# PMTControl.net
KiCad netlist of a schematic drawn in Altium Designer
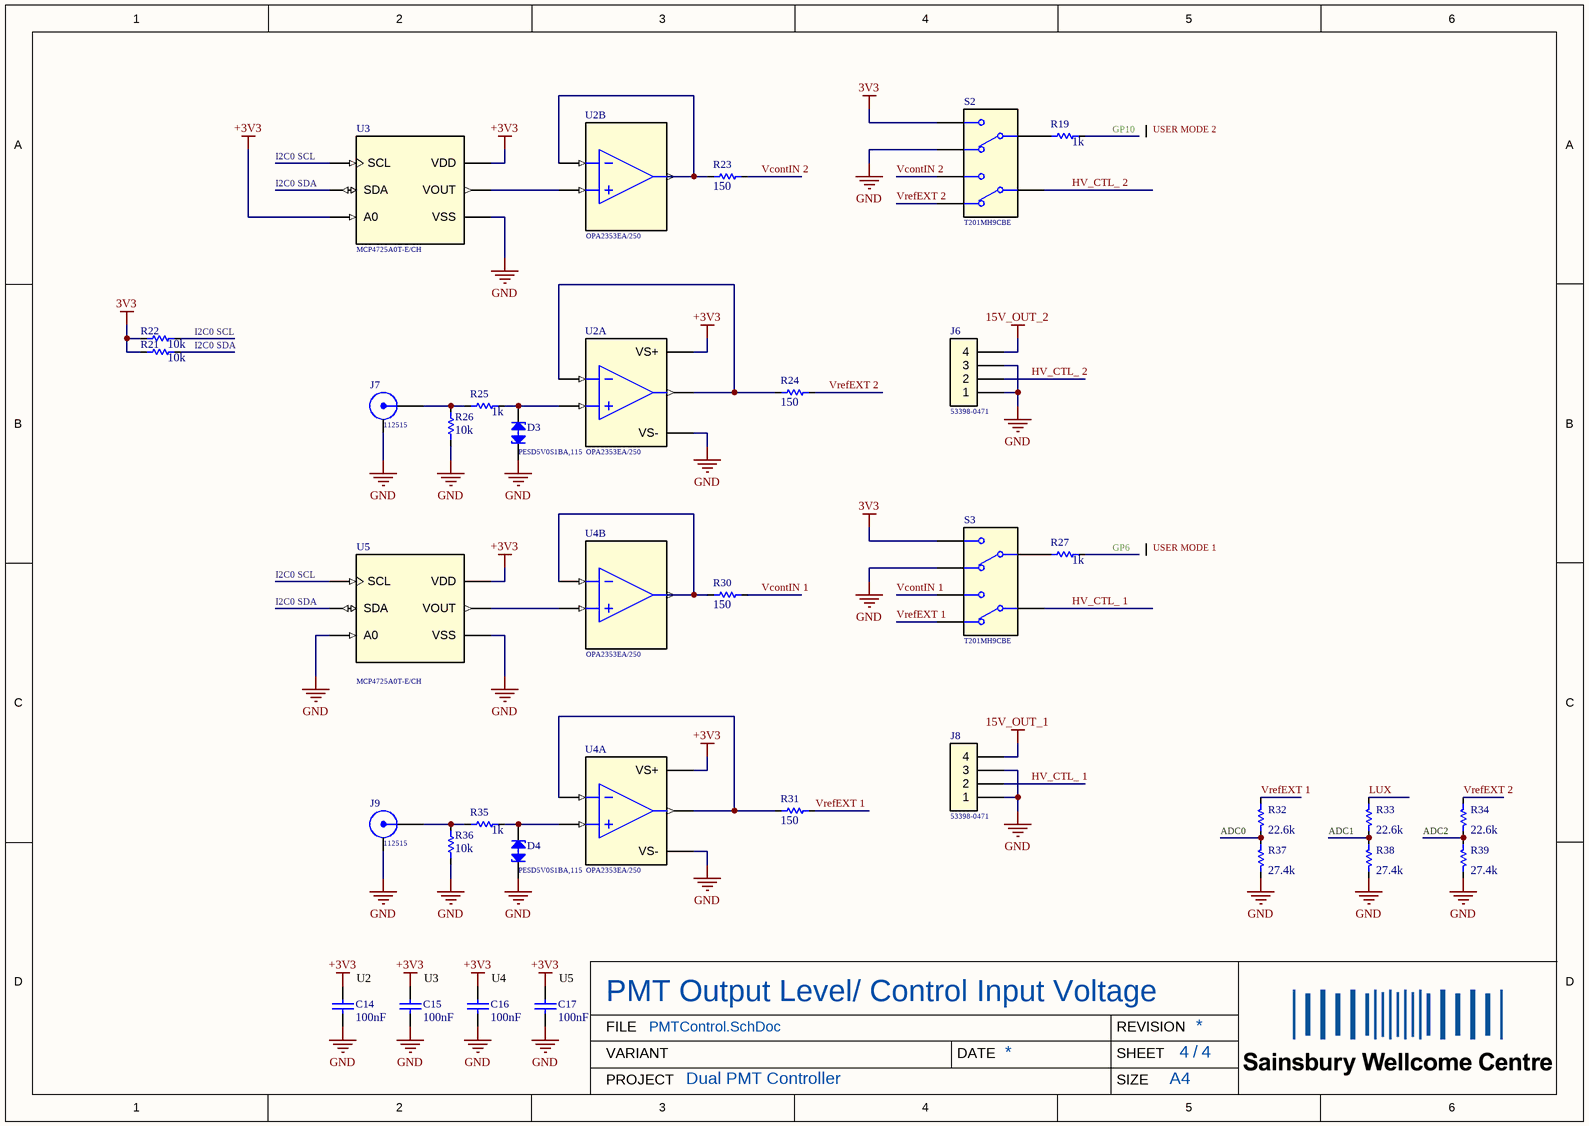
[diagram p0: PMTControl.SchDoc]

(export (version "E")
  (design (tool "Eeschema 10.0.6"))
  (components
    (comp (ref "C14")
      (value "100nF")
      (footprint "FP-GRM188-0_1-e0_2_0_5-IPC_B")
      (description "0.1µF ±10% 100V Ceramic Capacitor X7R 0603 (1608 Metric)")
      (fields (field (name "TOLERANCE") "10%") (field (name "VOLTAGE") "100V"))
      (libsource (lib "Sainsbury Wellcome Centre") (part "Cap"))
    )
    (comp (ref "C15")
      (value "100nF")
      (footprint "FP-GRM188-0_1-e0_2_0_5-IPC_B")
      (description "0.1µF ±10% 100V Ceramic Capacitor X7R 0603 (1608 Metric)")
      (fields (field (name "TOLERANCE") "10%") (field (name "VOLTAGE") "100V"))
      (libsource (lib "Sainsbury Wellcome Centre") (part "Cap"))
    )
    (comp (ref "C16")
      (value "100nF")
      (footprint "FP-GRM188-0_1-e0_2_0_5-IPC_B")
      (description "0.1µF ±10% 100V Ceramic Capacitor X7R 0603 (1608 Metric)")
      (fields (field (name "TOLERANCE") "10%") (field (name "VOLTAGE") "100V"))
      (libsource (lib "Sainsbury Wellcome Centre") (part "Cap"))
    )
    (comp (ref "C17")
      (value "100nF")
      (footprint "FP-GRM188-0_1-e0_2_0_5-IPC_B")
      (description "0.1µF ±10% 100V Ceramic Capacitor X7R 0603 (1608 Metric)")
      (fields (field (name "TOLERANCE") "10%") (field (name "VOLTAGE") "100V"))
      (libsource (lib "Sainsbury Wellcome Centre") (part "Cap"))
    )
    (comp (ref "D3")
      (value "PESD5V0S1BA,115")
      (footprint "FP-SOD323-CA-IPC_B")
      (description "Trans Voltage Suppressor Diode, 130W, 5V V(RWM), Bidirectional, 1 Element, Silicon")
      (libsource (lib "Sainsbury Wellcome Centre") (part "BI-ESD"))
    )
    (comp (ref "D4")
      (value "PESD5V0S1BA,115")
      (footprint "FP-SOD323-CA-IPC_B")
      (description "Trans Voltage Suppressor Diode, 130W, 5V V(RWM), Bidirectional, 1 Element, Silicon")
      (libsource (lib "Sainsbury Wellcome Centre") (part "BI-ESD"))
    )
    (comp (ref "J6")
      (value "53398-0471")
      (footprint "FP-533980471-MFG")
      (libsource (lib "Sainsbury Wellcome Centre") (part "Jack 4x1"))
    )
    (comp (ref "J7")
      (value "112515")
      (footprint "AMP_112515")
      (description "RF BNC Connector, Female, Board Mount, Solder Terminal, Jack")
      (libsource (lib "Sainsbury Wellcome Centre") (part "RF-Jack-V2"))
    )
    (comp (ref "J8")
      (value "53398-0471")
      (footprint "FP-533980471-MFG")
      (libsource (lib "Sainsbury Wellcome Centre") (part "Jack 4x1"))
    )
    (comp (ref "J9")
      (value "112515")
      (footprint "AMP_112515")
      (description "RF BNC Connector, Female, Board Mount, Solder Terminal, Jack")
      (libsource (lib "Sainsbury Wellcome Centre") (part "RF-Jack-V2"))
    )
    (comp (ref "R19")
      (value "1k")
      (footprint "FP-CPF0603-IPC_B")
      (description "Surface Mount Resistor 1k Ohm 1/16 W 0.1% 0603 (1608 Metric)")
      (fields (field (name "TOLERANCE") "0.1%") (field (name "Comment") "R0603-1k-1/16W-0.1%"))
      (libsource (lib "Sainsbury Wellcome Centre") (part "Res"))
    )
    (comp (ref "R21")
      (value "10k")
      (footprint "FP-CPF0603-IPC_B")
      (description "Surface Mount Resistor 10k Ohm 1/16 W 0.1% 0603 (1608 Metric)")
      (fields (field (name "TOLERANCE") "0.1%") (field (name "Comment") "R0603-10k-1/16W-0.1%"))
      (libsource (lib "Sainsbury Wellcome Centre") (part "Res"))
    )
    (comp (ref "R22")
      (value "10k")
      (footprint "FP-CPF0603-IPC_B")
      (description "Surface Mount Resistor 10k Ohm 1/16 W 0.1% 0603 (1608 Metric)")
      (fields (field (name "TOLERANCE") "0.1%") (field (name "Comment") "R0603-10k-1/16W-0.1%"))
      (libsource (lib "Sainsbury Wellcome Centre") (part "Res"))
    )
    (comp (ref "R23")
      (value "150")
      (footprint "FP-CPF0603-IPC_B")
      (description "Surface Mount Resistor 150 Ohm 1/16 W 0.1% 0603 (1608 Metric)")
      (fields (field (name "TOLERANCE") "0.1%") (field (name "Comment") "R0603-150R-1/16W-0.1%"))
      (libsource (lib "Sainsbury Wellcome Centre") (part "Res"))
    )
    (comp (ref "R24")
      (value "150")
      (footprint "FP-CPF0603-IPC_B")
      (description "Surface Mount Resistor 150 Ohm 1/16 W 0.1% 0603 (1608 Metric)")
      (fields (field (name "TOLERANCE") "0.1%") (field (name "Comment") "R0603-150R-1/16W-0.1%"))
      (libsource (lib "Sainsbury Wellcome Centre") (part "Res"))
    )
    (comp (ref "R25")
      (value "1k")
      (footprint "FP-CPF0603-IPC_B")
      (description "Surface Mount Resistor 1k Ohm 1/16 W 0.1% 0603 (1608 Metric)")
      (fields (field (name "TOLERANCE") "0.1%") (field (name "Comment") "R0603-1k-1/16W-0.1%"))
      (libsource (lib "Sainsbury Wellcome Centre") (part "Res"))
    )
    (comp (ref "R26")
      (value "10k")
      (footprint "FP-CPF0603-IPC_B")
      (description "Surface Mount Resistor 10k Ohm 1/16 W 0.1% 0603 (1608 Metric)")
      (fields (field (name "TOLERANCE") "0.1%") (field (name "Comment") "R0603-10k-1/16W-0.1%"))
      (libsource (lib "Sainsbury Wellcome Centre") (part "Res"))
    )
    (comp (ref "R27")
      (value "1k")
      (footprint "FP-CPF0603-IPC_B")
      (description "Surface Mount Resistor 1k Ohm 1/16 W 0.1% 0603 (1608 Metric)")
      (fields (field (name "TOLERANCE") "0.1%") (field (name "Comment") "R0603-1k-1/16W-0.1%"))
      (libsource (lib "Sainsbury Wellcome Centre") (part "Res"))
    )
    (comp (ref "R30")
      (value "150")
      (footprint "FP-CPF0603-IPC_B")
      (description "Surface Mount Resistor 150 Ohm 1/16 W 0.1% 0603 (1608 Metric)")
      (fields (field (name "TOLERANCE") "0.1%") (field (name "Comment") "R0603-150R-1/16W-0.1%"))
      (libsource (lib "Sainsbury Wellcome Centre") (part "Res"))
    )
    (comp (ref "R31")
      (value "150")
      (footprint "FP-CPF0603-IPC_B")
      (description "Surface Mount Resistor 150 Ohm 1/16 W 0.1% 0603 (1608 Metric)")
      (fields (field (name "TOLERANCE") "0.1%") (field (name "Comment") "R0603-150R-1/16W-0.1%"))
      (libsource (lib "Sainsbury Wellcome Centre") (part "Res"))
    )
    (comp (ref "R32")
      (value "22.6k")
      (footprint "FP-CPF0603-IPC_B")
      (description "Surface Mount Resistor 22.6k Ohm 1/16 W 0.1% 0603 (1608 Metric)")
      (fields (field (name "TOLERANCE") "0.1%") (field (name "Comment") "R0603-22k6-1/16W-0.1%"))
      (libsource (lib "Sainsbury Wellcome Centre") (part "Res"))
    )
    (comp (ref "R33")
      (value "22.6k")
      (footprint "FP-CPF0603-IPC_B")
      (description "Surface Mount Resistor 22.6k Ohm 1/16 W 0.1% 0603 (1608 Metric)")
      (fields (field (name "TOLERANCE") "0.1%") (field (name "Comment") "R0603-22k6-1/16W-0.1%"))
      (libsource (lib "Sainsbury Wellcome Centre") (part "Res"))
    )
    (comp (ref "R34")
      (value "22.6k")
      (footprint "FP-CPF0603-IPC_B")
      (description "Surface Mount Resistor 22.6k Ohm 1/16 W 0.1% 0603 (1608 Metric)")
      (fields (field (name "TOLERANCE") "0.1%") (field (name "Comment") "R0603-22k6-1/16W-0.1%"))
      (libsource (lib "Sainsbury Wellcome Centre") (part "Res"))
    )
    (comp (ref "R35")
      (value "1k")
      (footprint "FP-CPF0603-IPC_B")
      (description "Surface Mount Resistor 1k Ohm 1/16 W 0.1% 0603 (1608 Metric)")
      (fields (field (name "TOLERANCE") "0.1%") (field (name "Comment") "R0603-1k-1/16W-0.1%"))
      (libsource (lib "Sainsbury Wellcome Centre") (part "Res"))
    )
    (comp (ref "R36")
      (value "10k")
      (footprint "FP-CPF0603-IPC_B")
      (description "Surface Mount Resistor 10k Ohm 1/16 W 0.1% 0603 (1608 Metric)")
      (fields (field (name "TOLERANCE") "0.1%") (field (name "Comment") "R0603-10k-1/16W-0.1%"))
      (libsource (lib "Sainsbury Wellcome Centre") (part "Res"))
    )
    (comp (ref "R37")
      (value "27.4k")
      (footprint "FP-CPF0603-IPC_B")
      (description "Surface Mount Resistor 27.4k Ohm 1/16 W 0.1% 0603 (1608 Metric)")
      (fields (field (name "TOLERANCE") "0.1%") (field (name "Comment") "R0603-27k4-1/16W-0.1%"))
      (libsource (lib "Sainsbury Wellcome Centre") (part "Res"))
    )
    (comp (ref "R38")
      (value "27.4k")
      (footprint "FP-CPF0603-IPC_B")
      (description "Surface Mount Resistor 27.4k Ohm 1/16 W 0.1% 0603 (1608 Metric)")
      (fields (field (name "TOLERANCE") "0.1%") (field (name "Comment") "R0603-27k4-1/16W-0.1%"))
      (libsource (lib "Sainsbury Wellcome Centre") (part "Res"))
    )
    (comp (ref "R39")
      (value "27.4k")
      (footprint "FP-CPF0603-IPC_B")
      (description "Surface Mount Resistor 27.4k Ohm 1/16 W 0.1% 0603 (1608 Metric)")
      (fields (field (name "TOLERANCE") "0.1%") (field (name "Comment") "R0603-27k4-1/16W-0.1%"))
      (libsource (lib "Sainsbury Wellcome Centre") (part "Res"))
    )
    (comp (ref "S2")
      (value "T201MH9CBE")
      (footprint "SWITCH_T201MH9CBE")
      (libsource (lib "Sainsbury Wellcome Centre") (part "T201MH9CBE"))
    )
    (comp (ref "S3")
      (value "T201MH9CBE")
      (footprint "SWITCH_T201MH9CBE")
      (libsource (lib "Sainsbury Wellcome Centre") (part "T201MH9CBE"))
    )
    (comp (ref "U2")
      (value "OPA2353EA/250")
      (footprint "DGK0008A_N")
      (description "Operational Amplifier, 2 Func, 8000uV Offset-Max, CMOS, PDSO8")
      (libsource (lib "Sainsbury Wellcome Centre") (part "TI-OPA-8_2"))
    )
    (comp (ref "U3")
      (value "MCP4725A0T-E/CH")
      (footprint "FP-C04-028-CHY-MFG")
      (description "DAC 1-CH Resistor-String 12-bit 6-Pin SOT-23A T/R")
      (libsource (lib "Sainsbury Wellcome Centre") (part "13d1b9b03173b6bd00baa384b893ce8"))
    )
    (comp (ref "U4")
      (value "OPA2353EA/250")
      (footprint "DGK0008A_N")
      (description "Operational Amplifier, 2 Func, 8000uV Offset-Max, CMOS, PDSO8")
      (libsource (lib "Sainsbury Wellcome Centre") (part "TI-OPA-8_2"))
    )
    (comp (ref "U5")
      (value "MCP4725A0T-E/CH")
      (footprint "FP-C04-028-CHY-MFG")
      (description "DAC 1-CH Resistor-String 12-bit 6-Pin SOT-23A T/R")
      (libsource (lib "Sainsbury Wellcome Centre") (part "13d1b9b03173b6bd00baa384b893ce8"))
    )
  )
  (nets
    (net (code "1") (name "+3V3") (class "Default")
      (node (ref "C14") (pin "2") (pinfunction "2_2") (pintype "passive"))
      (node (ref "C15") (pin "2") (pinfunction "2_2") (pintype "passive"))
      (node (ref "C16") (pin "2") (pinfunction "2_2") (pintype "passive"))
      (node (ref "C17") (pin "2") (pinfunction "2_2") (pintype "passive"))
      (node (ref "U2") (pin "8") (pinfunction "VS+_8") (pintype "power_in"))
      (node (ref "U3") (pin "3") (pinfunction "VDD_3") (pintype "power_in"))
      (node (ref "U3") (pin "6") (pinfunction "A0_6") (pintype "input"))
      (node (ref "U4") (pin "8") (pinfunction "VS+_8") (pintype "power_in"))
      (node (ref "U5") (pin "3") (pinfunction "VDD_3") (pintype "power_in"))
    )
    (net (code "2") (name "/ADC0") (class "Default")
      (node (ref "R32") (pin "1") (pinfunction "1_1") (pintype "passive"))
      (node (ref "R37") (pin "2") (pinfunction "2_2") (pintype "passive"))
    )
    (net (code "3") (name "/ADC1") (class "Default")
      (node (ref "R33") (pin "1") (pinfunction "1_1") (pintype "passive"))
      (node (ref "R38") (pin "2") (pinfunction "2_2") (pintype "passive"))
    )
    (net (code "4") (name "/ADC2") (class "Default")
      (node (ref "R34") (pin "1") (pinfunction "1_1") (pintype "passive"))
      (node (ref "R39") (pin "2") (pinfunction "2_2") (pintype "passive"))
    )
    (net (code "5") (name "/GP6") (class "Default")
      (node (ref "R27") (pin "2") (pinfunction "2_2") (pintype "passive"))
    )
    (net (code "6") (name "/GP10") (class "Default")
      (node (ref "R19") (pin "2") (pinfunction "2_2") (pintype "passive"))
    )
    (net (code "7") (name "/HV_CTL_ 1") (class "Default")
      (node (ref "J8") (pin "2") (pinfunction "2_2") (pintype "passive"))
      (node (ref "S3") (pin "5") (pinfunction "COMMON_5") (pintype "passive"))
    )
    (net (code "8") (name "/HV_CTL_ 2") (class "Default")
      (node (ref "J6") (pin "2") (pinfunction "2_2") (pintype "passive"))
      (node (ref "S2") (pin "5") (pinfunction "COMMON_5") (pintype "passive"))
    )
    (net (code "9") (name "/I2C0 SCL") (class "Default")
      (node (ref "R22") (pin "1") (pinfunction "1_1") (pintype "passive"))
      (node (ref "U3") (pin "5") (pinfunction "SCL_5") (pintype "input"))
      (node (ref "U5") (pin "5") (pinfunction "SCL_5") (pintype "input"))
    )
    (net (code "10") (name "/I2C0 SDA") (class "Default")
      (node (ref "R21") (pin "1") (pinfunction "1_1") (pintype "passive"))
      (node (ref "U3") (pin "4") (pinfunction "SDA_4") (pintype "bidirectional"))
      (node (ref "U5") (pin "4") (pinfunction "SDA_4") (pintype "bidirectional"))
    )
    (net (code "11") (name "/LUX") (class "Default")
      (node (ref "R33") (pin "2") (pinfunction "2_2") (pintype "passive"))
    )
    (net (code "12") (name "/VcontIN 1") (class "Default")
      (node (ref "R30") (pin "2") (pinfunction "2_2") (pintype "passive"))
      (node (ref "S3") (pin "4") (pinfunction "CHANNEL_A_4") (pintype "passive"))
    )
    (net (code "13") (name "/VcontIN 2") (class "Default")
      (node (ref "R23") (pin "2") (pinfunction "2_2") (pintype "passive"))
      (node (ref "S2") (pin "4") (pinfunction "CHANNEL_A_4") (pintype "passive"))
    )
    (net (code "14") (name "/VrefEXT 1") (class "Default")
      (node (ref "R31") (pin "2") (pinfunction "2_2") (pintype "passive"))
      (node (ref "R32") (pin "2") (pinfunction "2_2") (pintype "passive"))
      (node (ref "S3") (pin "6") (pinfunction "CHANNEL_B_6") (pintype "passive"))
    )
    (net (code "15") (name "/VrefEXT 2") (class "Default")
      (node (ref "R24") (pin "2") (pinfunction "2_2") (pintype "passive"))
      (node (ref "R34") (pin "2") (pinfunction "2_2") (pintype "passive"))
      (node (ref "S2") (pin "6") (pinfunction "CHANNEL_B_6") (pintype "passive"))
    )
    (net (code "16") (name "3V3") (class "Default")
      (node (ref "R21") (pin "2") (pinfunction "2_2") (pintype "passive"))
      (node (ref "R22") (pin "2") (pinfunction "2_2") (pintype "passive"))
      (node (ref "S2") (pin "1") (pinfunction "CHANNEL_A_1") (pintype "passive"))
      (node (ref "S3") (pin "1") (pinfunction "CHANNEL_A_1") (pintype "passive"))
    )
    (net (code "17") (name "15V_OUT_1") (class "Default")
      (node (ref "J8") (pin "4") (pinfunction "4_4") (pintype "passive"))
    )
    (net (code "18") (name "15V_OUT_2") (class "Default")
      (node (ref "J6") (pin "4") (pinfunction "4_4") (pintype "passive"))
    )
    (net (code "19") (name "GND") (class "Default")
      (node (ref "C14") (pin "1") (pinfunction "1_1") (pintype "passive"))
      (node (ref "C15") (pin "1") (pinfunction "1_1") (pintype "passive"))
      (node (ref "C16") (pin "1") (pinfunction "1_1") (pintype "passive"))
      (node (ref "C17") (pin "1") (pinfunction "1_1") (pintype "passive"))
      (node (ref "D3") (pin "1") (pinfunction "K1_1") (pintype "passive"))
      (node (ref "D4") (pin "1") (pinfunction "K1_1") (pintype "passive"))
      (node (ref "J6") (pin "1") (pinfunction "1_1") (pintype "passive"))
      (node (ref "J6") (pin "3") (pinfunction "3_3") (pintype "passive"))
      (node (ref "J7") (pin "2") (pinfunction "GND_2") (pintype "passive"))
      (node (ref "J8") (pin "1") (pinfunction "1_1") (pintype "passive"))
      (node (ref "J8") (pin "3") (pinfunction "3_3") (pintype "passive"))
      (node (ref "J9") (pin "2") (pinfunction "GND_2") (pintype "passive"))
      (node (ref "R26") (pin "1") (pinfunction "1_1") (pintype "passive"))
      (node (ref "R36") (pin "1") (pinfunction "1_1") (pintype "passive"))
      (node (ref "R37") (pin "1") (pinfunction "1_1") (pintype "passive"))
      (node (ref "R38") (pin "1") (pinfunction "1_1") (pintype "passive"))
      (node (ref "R39") (pin "1") (pinfunction "1_1") (pintype "passive"))
      (node (ref "S2") (pin "3") (pinfunction "CHANNEL_B_3") (pintype "passive"))
      (node (ref "S3") (pin "3") (pinfunction "CHANNEL_B_3") (pintype "passive"))
      (node (ref "U2") (pin "4") (pinfunction "VS-_4") (pintype "power_in"))
      (node (ref "U3") (pin "2") (pinfunction "VSS_2") (pintype "power_in"))
      (node (ref "U4") (pin "4") (pinfunction "VS-_4") (pintype "power_in"))
      (node (ref "U5") (pin "2") (pinfunction "VSS_2") (pintype "power_in"))
      (node (ref "U5") (pin "6") (pinfunction "A0_6") (pintype "input"))
    )
    (net (code "20") (name "Net-(D3-K2)") (class "Default")
      (node (ref "D3") (pin "2") (pinfunction "K2_2") (pintype "passive"))
      (node (ref "R25") (pin "2") (pinfunction "2_2") (pintype "passive"))
      (node (ref "U2") (pin "3") (pinfunction "IN+_3") (pintype "input"))
    )
    (net (code "21") (name "Net-(D4-K2)") (class "Default")
      (node (ref "D4") (pin "2") (pinfunction "K2_2") (pintype "passive"))
      (node (ref "R35") (pin "2") (pinfunction "2_2") (pintype "passive"))
      (node (ref "U4") (pin "3") (pinfunction "IN+_3") (pintype "input"))
    )
    (net (code "22") (name "Net-(J7-SIG)") (class "Default")
      (node (ref "J7") (pin "1") (pinfunction "SIG_1") (pintype "passive"))
      (node (ref "R25") (pin "1") (pinfunction "1_1") (pintype "passive"))
      (node (ref "R26") (pin "2") (pinfunction "2_2") (pintype "passive"))
    )
    (net (code "23") (name "Net-(J9-SIG)") (class "Default")
      (node (ref "J9") (pin "1") (pinfunction "SIG_1") (pintype "passive"))
      (node (ref "R35") (pin "1") (pinfunction "1_1") (pintype "passive"))
      (node (ref "R36") (pin "2") (pinfunction "2_2") (pintype "passive"))
    )
    (net (code "24") (name "Net-(R19-Pad1)") (class "Default")
      (node (ref "R19") (pin "1") (pinfunction "1_1") (pintype "passive"))
      (node (ref "S2") (pin "2") (pinfunction "COMMON_2") (pintype "passive"))
    )
    (net (code "25") (name "Net-(R27-Pad1)") (class "Default")
      (node (ref "R27") (pin "1") (pinfunction "1_1") (pintype "passive"))
      (node (ref "S3") (pin "2") (pinfunction "COMMON_2") (pintype "passive"))
    )
    (net (code "26") (name "Net-(U2A-IN-)") (class "Default")
      (node (ref "R24") (pin "1") (pinfunction "1_1") (pintype "passive"))
      (node (ref "U2") (pin "1") (pinfunction "OUT_1") (pintype "output"))
      (node (ref "U2") (pin "2") (pinfunction "IN-_2") (pintype "input"))
    )
    (net (code "27") (name "Net-(U2B-IN+)") (class "Default")
      (node (ref "U2") (pin "5") (pinfunction "IN+_5") (pintype "input"))
      (node (ref "U3") (pin "1") (pinfunction "VOUT_1") (pintype "output"))
    )
    (net (code "28") (name "Net-(U2B-IN-)") (class "Default")
      (node (ref "R23") (pin "1") (pinfunction "1_1") (pintype "passive"))
      (node (ref "U2") (pin "6") (pinfunction "IN-_6") (pintype "input"))
      (node (ref "U2") (pin "7") (pinfunction "OUT_7") (pintype "output"))
    )
    (net (code "29") (name "Net-(U4A-IN-)") (class "Default")
      (node (ref "R31") (pin "1") (pinfunction "1_1") (pintype "passive"))
      (node (ref "U4") (pin "1") (pinfunction "OUT_1") (pintype "output"))
      (node (ref "U4") (pin "2") (pinfunction "IN-_2") (pintype "input"))
    )
    (net (code "30") (name "Net-(U4B-IN+)") (class "Default")
      (node (ref "U4") (pin "5") (pinfunction "IN+_5") (pintype "input"))
      (node (ref "U5") (pin "1") (pinfunction "VOUT_1") (pintype "output"))
    )
    (net (code "31") (name "Net-(U4B-IN-)") (class "Default")
      (node (ref "R30") (pin "1") (pinfunction "1_1") (pintype "passive"))
      (node (ref "U4") (pin "6") (pinfunction "IN-_6") (pintype "input"))
      (node (ref "U4") (pin "7") (pinfunction "OUT_7") (pintype "output"))
    )
  )
)
